# Analog.net
KiCad netlist of a schematic drawn in Altium Designer
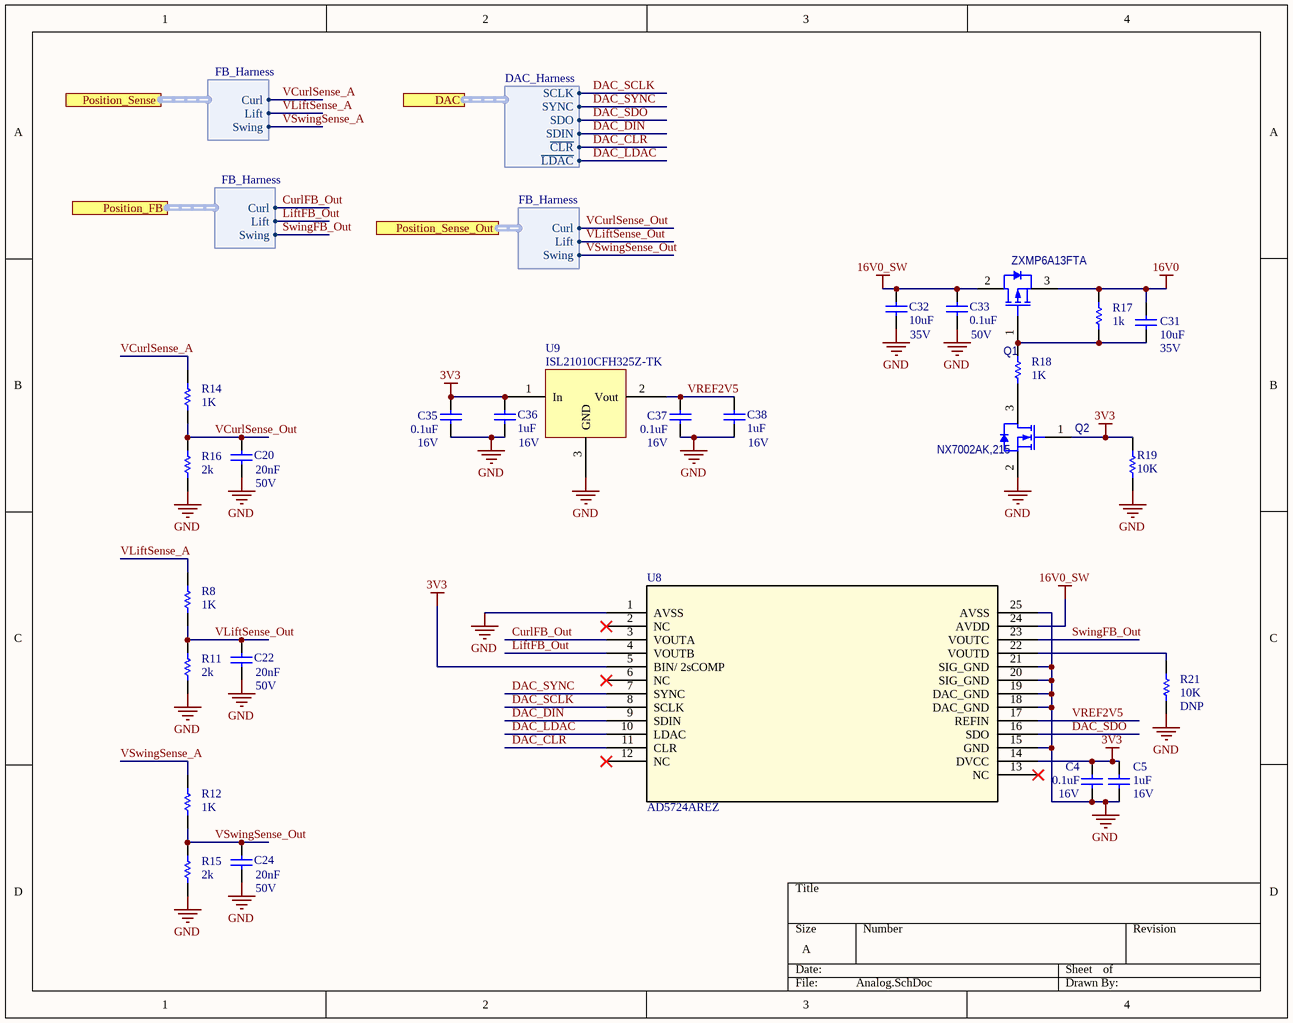
[diagram p0: Analog.SchDoc]

(export (version "E")
  (design (tool "Eeschema 10.0.6"))
  (components
    (comp (ref "C4")
      (value "0.1uF")
      (footprint "CAPC1005(0402)N")
      (description "CAP CER 0.1UF 16V X5R 0402")
      (fields (field (name "TOLERANCE") "±10%") (field (name "VOLTAGE - RATED") "16V"))
      (libsource (lib "GMLintLib") (part "CAP"))
    )
    (comp (ref "C5")
      (value "1uF")
      (footprint "CAPC1005(0402)N")
      (description "CAP")
      (fields (field (name "TOLERANCE") "±10%") (field (name "VOLTAGE - RATED") "16V"))
      (libsource (lib "GMLintLib") (part "CAP"))
    )
    (comp (ref "C20")
      (value "20nF")
      (footprint "0402")
      (description "Capacitor")
      (fields
        (field (name "VOLTAGE - RATED") "50V")
        (field (name "Comment") "Cap")
        (field (name "PUBLISHER") "Altium Limited")
      )
      (libsource (lib "Miscellaneous Devices") (part "Cap"))
    )
    (comp (ref "C22")
      (value "20nF")
      (footprint "0402")
      (description "Capacitor")
      (fields
        (field (name "VOLTAGE - RATED") "50V")
        (field (name "Comment") "Cap")
        (field (name "PUBLISHER") "Altium Limited")
      )
      (libsource (lib "Miscellaneous Devices") (part "Cap"))
    )
    (comp (ref "C24")
      (value "20nF")
      (footprint "0402")
      (description "Capacitor")
      (fields
        (field (name "VOLTAGE - RATED") "50V")
        (field (name "Comment") "Cap")
        (field (name "PUBLISHER") "Altium Limited")
      )
      (libsource (lib "Miscellaneous Devices") (part "Cap"))
    )
    (comp (ref "C31")
      (value "10uF")
      (footprint "CAPC2012X145N")
      (description "CAP")
      (fields (field (name "TOLERANCE") "±10%") (field (name "VOLTAGE - RATED") "35V"))
      (libsource (lib "GMLintLib") (part "CAP"))
    )
    (comp (ref "C32")
      (value "10uF")
      (footprint "CAPC2012X145N")
      (description "CAP")
      (fields (field (name "TOLERANCE") "±10%") (field (name "VOLTAGE - RATED") "35V"))
      (libsource (lib "GMLintLib") (part "CAP"))
    )
    (comp (ref "C33")
      (value "0.1uF")
      (footprint "CAPC1005(0402)N")
      (description "CAP CER 0.1UF 16V X5R 0402")
      (fields (field (name "TOLERANCE") "±10%") (field (name "VOLTAGE - RATED") "50V"))
      (libsource (lib "GMLintLib") (part "CAP"))
    )
    (comp (ref "C35")
      (value "0.1uF")
      (footprint "CAPC1005(0402)N")
      (description "CAP CER 0.1UF 16V X5R 0402")
      (fields (field (name "TOLERANCE") "±10%") (field (name "VOLTAGE - RATED") "16V"))
      (libsource (lib "GMLintLib") (part "CAP"))
    )
    (comp (ref "C36")
      (value "1uF")
      (footprint "CAPC1005(0402)N")
      (description "CAP")
      (fields (field (name "TOLERANCE") "±10%") (field (name "VOLTAGE - RATED") "16V"))
      (libsource (lib "GMLintLib") (part "CAP"))
    )
    (comp (ref "C37")
      (value "0.1uF")
      (footprint "CAPC1005(0402)N")
      (description "CAP CER 0.1UF 16V X5R 0402")
      (fields (field (name "TOLERANCE") "±10%") (field (name "VOLTAGE - RATED") "16V"))
      (libsource (lib "GMLintLib") (part "CAP"))
    )
    (comp (ref "C38")
      (value "1uF")
      (footprint "CAPC1005(0402)N")
      (description "CAP")
      (fields (field (name "TOLERANCE") "±10%") (field (name "VOLTAGE - RATED") "16V"))
      (libsource (lib "GMLintLib") (part "CAP"))
    )
    (comp (ref "Q1")
      (value "ZXMP6A13FTA")
      (footprint "*SOT95P230X110-3P")
      (description "MOSFET P-CH 20V 0.1A VMT3")
      (fields (field (name "MANUFACTURER PART NUMBER 1") "ZXMP6A13FTA"))
      (libsource (lib "ArtiphonPartLibrary") (part "RZM001P02T2L"))
    )
    (comp (ref "Q2")
      (value "NX7002AK,215")
      (footprint "*SOT95P230X110-3N")
      (description "MOSFET 60 V, Single N-chan Trench")
      (fields (field (name "MANUFACTURER PART NUMBER 1") "NX7002AK,215"))
      (libsource (lib "ArtiphonPartLibrary") (part "NX7002AKVL"))
    )
    (comp (ref "R8")
      (value "1K")
      (footprint "0402")
      (description "Resistor")
      (fields (field (name "Comment") "Res1") (field (name "PUBLISHER") "Altium Limited"))
      (libsource (lib "Miscellaneous Devices") (part "Res1"))
    )
    (comp (ref "R11")
      (value "2k")
      (footprint "0402")
      (description "Resistor")
      (fields (field (name "Comment") "Res1") (field (name "PUBLISHER") "Altium Limited"))
      (libsource (lib "Miscellaneous Devices") (part "Res1"))
    )
    (comp (ref "R12")
      (value "1K")
      (footprint "0402")
      (description "Resistor")
      (fields (field (name "Comment") "Res1") (field (name "PUBLISHER") "Altium Limited"))
      (libsource (lib "Miscellaneous Devices") (part "Res1"))
    )
    (comp (ref "R14")
      (value "1K")
      (footprint "0402")
      (description "Resistor")
      (fields (field (name "Comment") "Res1") (field (name "PUBLISHER") "Altium Limited"))
      (libsource (lib "Miscellaneous Devices") (part "Res1"))
    )
    (comp (ref "R15")
      (value "2k")
      (footprint "0402")
      (description "Resistor")
      (fields (field (name "Comment") "Res1") (field (name "PUBLISHER") "Altium Limited"))
      (libsource (lib "Miscellaneous Devices") (part "Res1"))
    )
    (comp (ref "R16")
      (value "2k")
      (footprint "0402")
      (description "Resistor")
      (fields (field (name "Comment") "Res1") (field (name "PUBLISHER") "Altium Limited"))
      (libsource (lib "Miscellaneous Devices") (part "Res1"))
    )
    (comp (ref "R17")
      (value "1k")
      (footprint "0402")
      (description "Resistor")
      (fields (field (name "Comment") "Res1") (field (name "PUBLISHER") "Altium Limited"))
      (libsource (lib "Miscellaneous Devices") (part "Res1"))
    )
    (comp (ref "R18")
      (value "1K")
      (footprint "0402")
      (description "Resistor")
      (fields (field (name "Comment") "Res1") (field (name "PUBLISHER") "Altium Limited"))
      (libsource (lib "Miscellaneous Devices") (part "Res1"))
    )
    (comp (ref "R19")
      (value "10K")
      (footprint "RESC1005(0402)N")
      (description "Resistor, Chip")
      (libsource (lib "GMLintLib") (part "RES"))
    )
    (comp (ref "R21")
      (value "10K")
      (footprint "0402")
      (description "Resistor")
      (fields
        (field (name "DNP") "DNP")
        (field (name "Comment") "Res1")
        (field (name "PUBLISHER") "Altium Limited")
      )
      (libsource (lib "Miscellaneous Devices") (part "Res1"))
    )
    (comp (ref "U8")
      (value "AD5724AREZ")
      (footprint "RE_24")
      (description "No Description Available")
      (fields (field (name "COPYRIGHT") "Copyright (C) 2018 Accelerated Designs. All rights reserved"))
      (libsource (lib "LegBoard") (part "AD5724AREZ"))
    )
    (comp (ref "U9")
      (value "ISL21010CFH325Z-TK")
      (footprint "SOT95P237X111-3N")
      (libsource (lib "LegBoard") (part "ISL21010CFH325Z-TK"))
    )
  )
  (nets
    (net (code "3") (name "/CurlFB_Out") (class "Default")
      (node (ref "U8") (pin "3") (pinfunction "VOUTA_3") (pintype "passive"))
    )
    (net (code "4") (name "/DAC_DIN") (class "Default")
      (node (ref "U8") (pin "9") (pinfunction "SDIN_9") (pintype "passive"))
    )
    (net (code "5") (name "/DAC_SCLK") (class "Default")
      (node (ref "U8") (pin "8") (pinfunction "SCLK_8") (pintype "passive"))
    )
    (net (code "6") (name "/DAC_SDO") (class "Default")
      (node (ref "U8") (pin "16") (pinfunction "SDO_16") (pintype "passive"))
    )
    (net (code "7") (name "/DAC_SYNC") (class "Default")
      (node (ref "U8") (pin "7") (pinfunction "SYNC_7") (pintype "passive"))
    )
    (net (code "8") (name "/DAC_~{CLR}") (class "Default")
      (node (ref "U8") (pin "11") (pinfunction "CLR_11") (pintype "passive"))
    )
    (net (code "9") (name "/DAC_~{LDAC}") (class "Default")
      (node (ref "U8") (pin "10") (pinfunction "LDAC_10") (pintype "passive"))
    )
    (net (code "10") (name "/LiftFB_Out") (class "Default")
      (node (ref "U8") (pin "4") (pinfunction "VOUTB_4") (pintype "passive"))
    )
    (net (code "11") (name "/SwingFB_Out") (class "Default")
      (node (ref "U8") (pin "23") (pinfunction "VOUTC_23") (pintype "passive"))
    )
    (net (code "12") (name "/VCurlSense_A") (class "Default")
      (node (ref "R14") (pin "2") (pinfunction "2_2") (pintype "passive"))
    )
    (net (code "13") (name "/VCurlSense_Out") (class "Default")
      (node (ref "C20") (pin "2") (pinfunction "2_2") (pintype "passive"))
      (node (ref "R14") (pin "1") (pinfunction "1_1") (pintype "passive"))
      (node (ref "R16") (pin "2") (pinfunction "2_2") (pintype "passive"))
    )
    (net (code "14") (name "/VLiftSense_A") (class "Default")
      (node (ref "R8") (pin "2") (pinfunction "2_2") (pintype "passive"))
    )
    (net (code "15") (name "/VLiftSense_Out") (class "Default")
      (node (ref "C22") (pin "2") (pinfunction "2_2") (pintype "passive"))
      (node (ref "R11") (pin "2") (pinfunction "2_2") (pintype "passive"))
      (node (ref "R8") (pin "1") (pinfunction "1_1") (pintype "passive"))
    )
    (net (code "16") (name "/VREF2V5") (class "Default")
      (node (ref "C37") (pin "2") (pinfunction "2_2") (pintype "passive"))
      (node (ref "C38") (pin "2") (pinfunction "2_2") (pintype "passive"))
      (node (ref "U8") (pin "17") (pinfunction "REFIN_17") (pintype "passive"))
      (node (ref "U9") (pin "2") (pinfunction "Vout_2") (pintype "passive"))
    )
    (net (code "17") (name "/VSwingSense_A") (class "Default")
      (node (ref "R12") (pin "2") (pinfunction "2_2") (pintype "passive"))
    )
    (net (code "18") (name "/VSwingSense_Out") (class "Default")
      (node (ref "C24") (pin "2") (pinfunction "2_2") (pintype "passive"))
      (node (ref "R12") (pin "1") (pinfunction "1_1") (pintype "passive"))
      (node (ref "R15") (pin "2") (pinfunction "2_2") (pintype "passive"))
    )
    (net (code "21") (name "3V3") (class "Default")
      (node (ref "C35") (pin "2") (pinfunction "2_2") (pintype "passive"))
      (node (ref "C36") (pin "2") (pinfunction "2_2") (pintype "passive"))
      (node (ref "C4") (pin "2") (pinfunction "2_2") (pintype "passive"))
      (node (ref "C5") (pin "2") (pinfunction "2_2") (pintype "passive"))
      (node (ref "Q2") (pin "1") (pinfunction "G1_1") (pintype "passive"))
      (node (ref "R19") (pin "2") (pinfunction "2_2") (pintype "passive"))
      (node (ref "U8") (pin "14") (pinfunction "DVCC_14") (pintype "power_in"))
      (node (ref "U8") (pin "5") (pinfunction "BIN/_2sCOMP_5") (pintype "passive"))
      (node (ref "U9") (pin "1") (pinfunction "In_1") (pintype "passive"))
    )
    (net (code "22") (name "16V0") (class "Default")
      (node (ref "C31") (pin "2") (pinfunction "2_2") (pintype "passive"))
      (node (ref "Q1") (pin "3") (pinfunction "S1_3") (pintype "passive"))
      (node (ref "R17") (pin "2") (pinfunction "2_2") (pintype "passive"))
    )
    (net (code "23") (name "16V0_SW") (class "Default")
      (node (ref "C32") (pin "1") (pinfunction "1_1") (pintype "passive"))
      (node (ref "C33") (pin "2") (pinfunction "2_2") (pintype "passive"))
      (node (ref "Q1") (pin "2") (pinfunction "D1_2") (pintype "passive"))
      (node (ref "U8") (pin "24") (pinfunction "AVDD_24") (pintype "power_in"))
    )
    (net (code "24") (name "GND") (class "Default")
      (node (ref "C20") (pin "1") (pinfunction "1_1") (pintype "passive"))
      (node (ref "C22") (pin "1") (pinfunction "1_1") (pintype "passive"))
      (node (ref "C24") (pin "1") (pinfunction "1_1") (pintype "passive"))
      (node (ref "C32") (pin "2") (pinfunction "2_2") (pintype "passive"))
      (node (ref "C33") (pin "1") (pinfunction "1_1") (pintype "passive"))
      (node (ref "C35") (pin "1") (pinfunction "1_1") (pintype "passive"))
      (node (ref "C36") (pin "1") (pinfunction "1_1") (pintype "passive"))
      (node (ref "C37") (pin "1") (pinfunction "1_1") (pintype "passive"))
      (node (ref "C38") (pin "1") (pinfunction "1_1") (pintype "passive"))
      (node (ref "C4") (pin "1") (pinfunction "1_1") (pintype "passive"))
      (node (ref "C5") (pin "1") (pinfunction "1_1") (pintype "passive"))
      (node (ref "Q2") (pin "2") (pinfunction "S1_2") (pintype "passive"))
      (node (ref "R11") (pin "1") (pinfunction "1_1") (pintype "passive"))
      (node (ref "R15") (pin "1") (pinfunction "1_1") (pintype "passive"))
      (node (ref "R16") (pin "1") (pinfunction "1_1") (pintype "passive"))
      (node (ref "R19") (pin "1") (pinfunction "1_1") (pintype "passive"))
      (node (ref "R21") (pin "1") (pinfunction "1_1") (pintype "passive"))
      (node (ref "U8") (pin "1") (pinfunction "AVSS_1") (pintype "passive"))
      (node (ref "U8") (pin "15") (pinfunction "GND_15") (pintype "passive"))
      (node (ref "U8") (pin "18") (pinfunction "DAC_GND_18") (pintype "passive"))
      (node (ref "U8") (pin "19") (pinfunction "DAC_GND_19") (pintype "passive"))
      (node (ref "U8") (pin "20") (pinfunction "SIG_GND_20") (pintype "passive"))
      (node (ref "U8") (pin "21") (pinfunction "SIG_GND_21") (pintype "passive"))
      (node (ref "U8") (pin "25") (pinfunction "AVSS_25") (pintype "power_in"))
      (node (ref "U9") (pin "3") (pinfunction "GND_3") (pintype "passive"))
    )
    (net (code "25") (name "Net-(Q1-G1)") (class "Default")
      (node (ref "C31") (pin "1") (pinfunction "1_1") (pintype "passive"))
      (node (ref "Q1") (pin "1") (pinfunction "G1_1") (pintype "passive"))
      (node (ref "R17") (pin "1") (pinfunction "1_1") (pintype "passive"))
      (node (ref "R18") (pin "2") (pinfunction "2_2") (pintype "passive"))
    )
    (net (code "26") (name "Net-(Q2-D1)") (class "Default")
      (node (ref "Q2") (pin "3") (pinfunction "D1_3") (pintype "passive"))
      (node (ref "R18") (pin "1") (pinfunction "1_1") (pintype "passive"))
    )
    (net (code "27") (name "Net-(U8-VOUTD)") (class "Default")
      (node (ref "R21") (pin "2") (pinfunction "2_2") (pintype "passive"))
      (node (ref "U8") (pin "22") (pinfunction "VOUTD_22") (pintype "passive"))
    )
    (net (code "28") (name "unconnected-(U8-NC-Pad2)") (class "Default")
      (node (ref "U8") (pin "2") (pinfunction "NC_2") (pintype "passive+no_connect"))
    )
    (net (code "29") (name "unconnected-(U8-NC-Pad6)") (class "Default")
      (node (ref "U8") (pin "6") (pinfunction "NC_6") (pintype "passive+no_connect"))
    )
    (net (code "30") (name "unconnected-(U8-NC-Pad12)") (class "Default")
      (node (ref "U8") (pin "12") (pinfunction "NC_12") (pintype "passive+no_connect"))
    )
    (net (code "31") (name "unconnected-(U8-NC-Pad13)") (class "Default")
      (node (ref "U8") (pin "13") (pinfunction "NC_13") (pintype "passive+no_connect"))
    )
  )
)
